# Input_Protection.net
KiCad netlist of a schematic drawn in Altium Designer
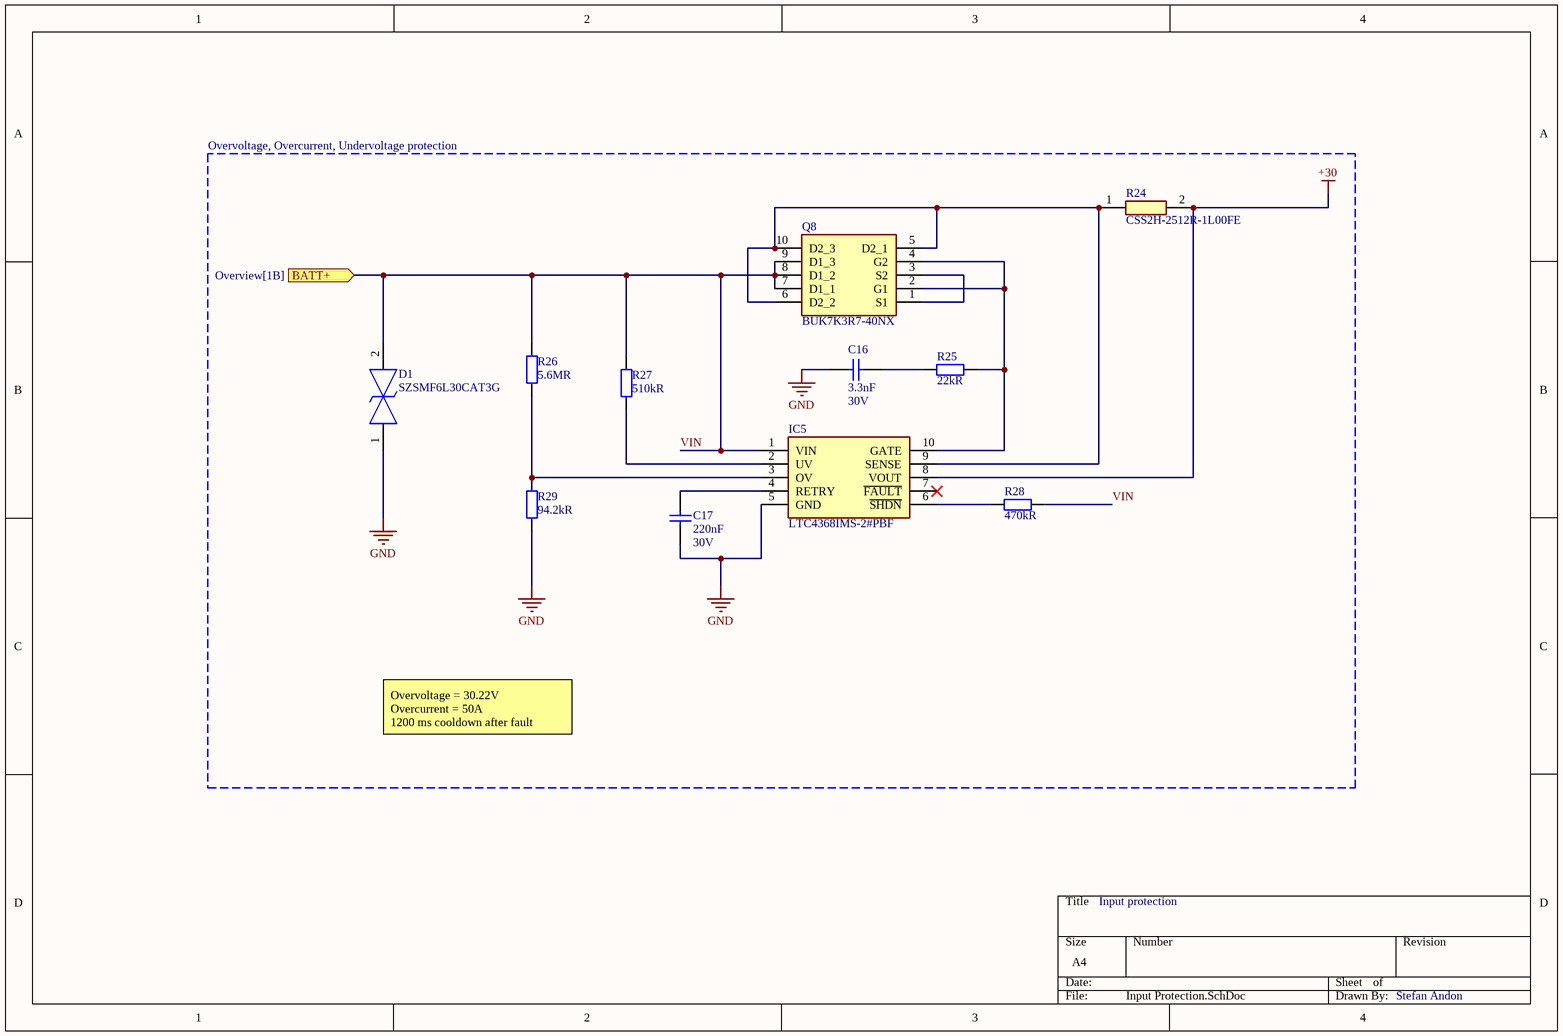
[diagram p0: Input Protection.SchDoc]

(export (version "E")
  (design (tool "Eeschema 10.0.6"))
  (components
    (comp (ref "C16")
      (value "3.3nF")
      (footprint "CAP_0603")
      (description "SMD Capacitor")
      (fields
        (field (name "TOLERANCE") "tbd")
        (field (name "VOLTAGE") "30V")
        (field (name "Comment") "Capacitor_SMD")
      )
      (libsource (lib "TUfast e") (part "SMD Capacitor"))
    )
    (comp (ref "C17")
      (value "220nF")
      (footprint "CAP_0603")
      (description "SMD Capacitor")
      (fields
        (field (name "TOLERANCE") "tbd")
        (field (name "VOLTAGE") "30V")
        (field (name "Comment") "Capacitor_SMD")
      )
      (libsource (lib "TUfast e") (part "SMD Capacitor"))
    )
    (comp (ref "D1")
      (value "SZSMF6L30CAT3G")
      (footprint "SamacSys:SMFA2005CA")
      (description "TVS Diode (Bi-directional)")
      (libsource (lib "*") (part "SZSMF6L30CAT3G"))
    )
    (comp (ref "IC5")
      (value "LTC4368IMS-2#PBF")
      (footprint "SamacSys:SOP50P490X110-10N")
      (description "Integrated Circuit")
      (fields (field (name "MOUSER PART NUMBER") "584-LTC4368IMS2PBF"))
      (libsource (lib "*") (part "LTC4368IMS-2#PBF"))
    )
    (comp (ref "Q8")
      (value "BUK7K3R7-40NX")
      (footprint "SamacSys:BUK7K29100EX")
      (description "MOSFET (N-Channel)")
      (libsource (lib "*") (part "BUK7K3R7-40NX"))
    )
    (comp (ref "R24")
      (value "CSS2H-2512R-1L00FE")
      (footprint "SamacSys:CSS2H2512R1L00FE")
      (description "Resistor")
      (fields (field (name "MOUSER PART NUMBER") "652-CSS2H2512R1L00FE"))
      (libsource (lib "*") (part "CSS2H-2512R-1L00FE"))
    )
    (comp (ref "R25")
      (value "22kR")
      (footprint "RES_0603")
      (fields
        (field (name "TOLERANCE") "tbd")
        (field (name "POWER") "7W")
        (field (name "Comment") "Resistor_SMD")
      )
      (libsource (lib "") (part "Resistor_2"))
    )
    (comp (ref "R26")
      (value "5.6MR")
      (footprint "RES_0603")
      (fields
        (field (name "TOLERANCE") "tbd")
        (field (name "POWER") "7W")
        (field (name "Comment") "Resistor_SMD")
      )
      (libsource (lib "TUfast e") (part "Resistor"))
    )
    (comp (ref "R27")
      (value "510kR")
      (footprint "RES_0603")
      (fields
        (field (name "TOLERANCE") "tbd")
        (field (name "POWER") "7W")
        (field (name "Comment") "Resistor_SMD")
      )
      (libsource (lib "TUfast e") (part "Resistor"))
    )
    (comp (ref "R28")
      (value "470kR")
      (footprint "RES_0603")
      (fields
        (field (name "TOLERANCE") "tbd")
        (field (name "POWER") "7W")
        (field (name "Comment") "Resistor_SMD")
      )
      (libsource (lib "") (part "Resistor_1"))
    )
    (comp (ref "R29")
      (value "94.2kR")
      (footprint "RES_0603")
      (fields
        (field (name "TOLERANCE") "tbd")
        (field (name "POWER") "7W")
        (field (name "Comment") "Resistor_SMD")
      )
      (libsource (lib "TUfast e") (part "Resistor"))
    )
  )
  (nets
    (net (code "1") (name "+30") (class "Default")
      (node (ref "IC5") (pin "8") (pinfunction "VOUT_8") (pintype "passive"))
      (node (ref "R24") (pin "2") (pinfunction "2_2") (pintype "passive"))
    )
    (net (code "2") (name "/VIN") (class "Default")
      (node (ref "D1") (pin "2") (pinfunction "2_2") (pintype "passive"))
      (node (ref "IC5") (pin "1") (pinfunction "VIN_1") (pintype "passive"))
      (node (ref "Q8") (pin "7") (pinfunction "D1_1_7") (pintype "passive"))
      (node (ref "Q8") (pin "8") (pinfunction "D1_2_8") (pintype "passive"))
      (node (ref "Q8") (pin "9") (pinfunction "D1_3_9") (pintype "passive"))
      (node (ref "R26") (pin "2") (pinfunction "2_2") (pintype "passive"))
      (node (ref "R27") (pin "2") (pinfunction "2_2") (pintype "passive"))
      (node (ref "R28") (pin "1") (pinfunction "1_1") (pintype "passive"))
    )
    (net (code "3") (name "GND") (class "Default")
      (node (ref "C16") (pin "2") (pinfunction "2_2") (pintype "passive"))
      (node (ref "C17") (pin "2") (pinfunction "2_2") (pintype "passive"))
      (node (ref "D1") (pin "1") (pinfunction "1_1") (pintype "passive"))
      (node (ref "IC5") (pin "5") (pinfunction "GND_5") (pintype "passive"))
      (node (ref "R29") (pin "1") (pinfunction "1_1") (pintype "passive"))
    )
    (net (code "4") (name "Net-(C16-Pad1)") (class "Default")
      (node (ref "C16") (pin "1") (pinfunction "1_1") (pintype "passive"))
      (node (ref "R25") (pin "1") (pinfunction "1_1") (pintype "passive"))
    )
    (net (code "5") (name "Net-(IC5-GATE)") (class "Default")
      (node (ref "IC5") (pin "10") (pinfunction "GATE_10") (pintype "passive"))
      (node (ref "Q8") (pin "2") (pinfunction "G1_2") (pintype "passive"))
      (node (ref "Q8") (pin "4") (pinfunction "G2_4") (pintype "passive"))
      (node (ref "R25") (pin "2") (pinfunction "2_2") (pintype "passive"))
    )
    (net (code "6") (name "Net-(IC5-OV)") (class "Default")
      (node (ref "IC5") (pin "3") (pinfunction "OV_3") (pintype "passive"))
      (node (ref "R26") (pin "1") (pinfunction "1_1") (pintype "passive"))
      (node (ref "R29") (pin "2") (pinfunction "2_2") (pintype "passive"))
    )
    (net (code "7") (name "Net-(IC5-RETRY)") (class "Default")
      (node (ref "C17") (pin "1") (pinfunction "1_1") (pintype "passive"))
      (node (ref "IC5") (pin "4") (pinfunction "RETRY_4") (pintype "passive"))
    )
    (net (code "8") (name "Net-(IC5-SENSE)") (class "Default")
      (node (ref "IC5") (pin "9") (pinfunction "SENSE_9") (pintype "passive"))
      (node (ref "Q8") (pin "10") (pinfunction "D2_3_10") (pintype "passive"))
      (node (ref "Q8") (pin "5") (pinfunction "D2_1_5") (pintype "passive"))
      (node (ref "Q8") (pin "6") (pinfunction "D2_2_6") (pintype "passive"))
      (node (ref "R24") (pin "1") (pinfunction "1_1") (pintype "passive"))
    )
    (net (code "9") (name "Net-(IC5-UV)") (class "Default")
      (node (ref "IC5") (pin "2") (pinfunction "UV_2") (pintype "passive"))
      (node (ref "R27") (pin "1") (pinfunction "1_1") (pintype "passive"))
    )
    (net (code "10") (name "Net-(IC5-~{SHDN})") (class "Default")
      (node (ref "IC5") (pin "6") (pinfunction "~{SHDN}_6") (pintype "passive"))
      (node (ref "R28") (pin "2") (pinfunction "2_2") (pintype "passive"))
    )
    (net (code "11") (name "Net-(Q8-S1)") (class "Default")
      (node (ref "Q8") (pin "1") (pinfunction "S1_1") (pintype "passive"))
      (node (ref "Q8") (pin "3") (pinfunction "S2_3") (pintype "passive"))
    )
    (net (code "12") (name "unconnected-(IC5-~{FAULT}-Pad7)") (class "Default")
      (node (ref "IC5") (pin "7") (pinfunction "~{FAULT}_7") (pintype "passive+no_connect"))
    )
  )
)
